# OPAMP_TESTER_2.net
KiCad netlist of a schematic drawn in Altium Designer
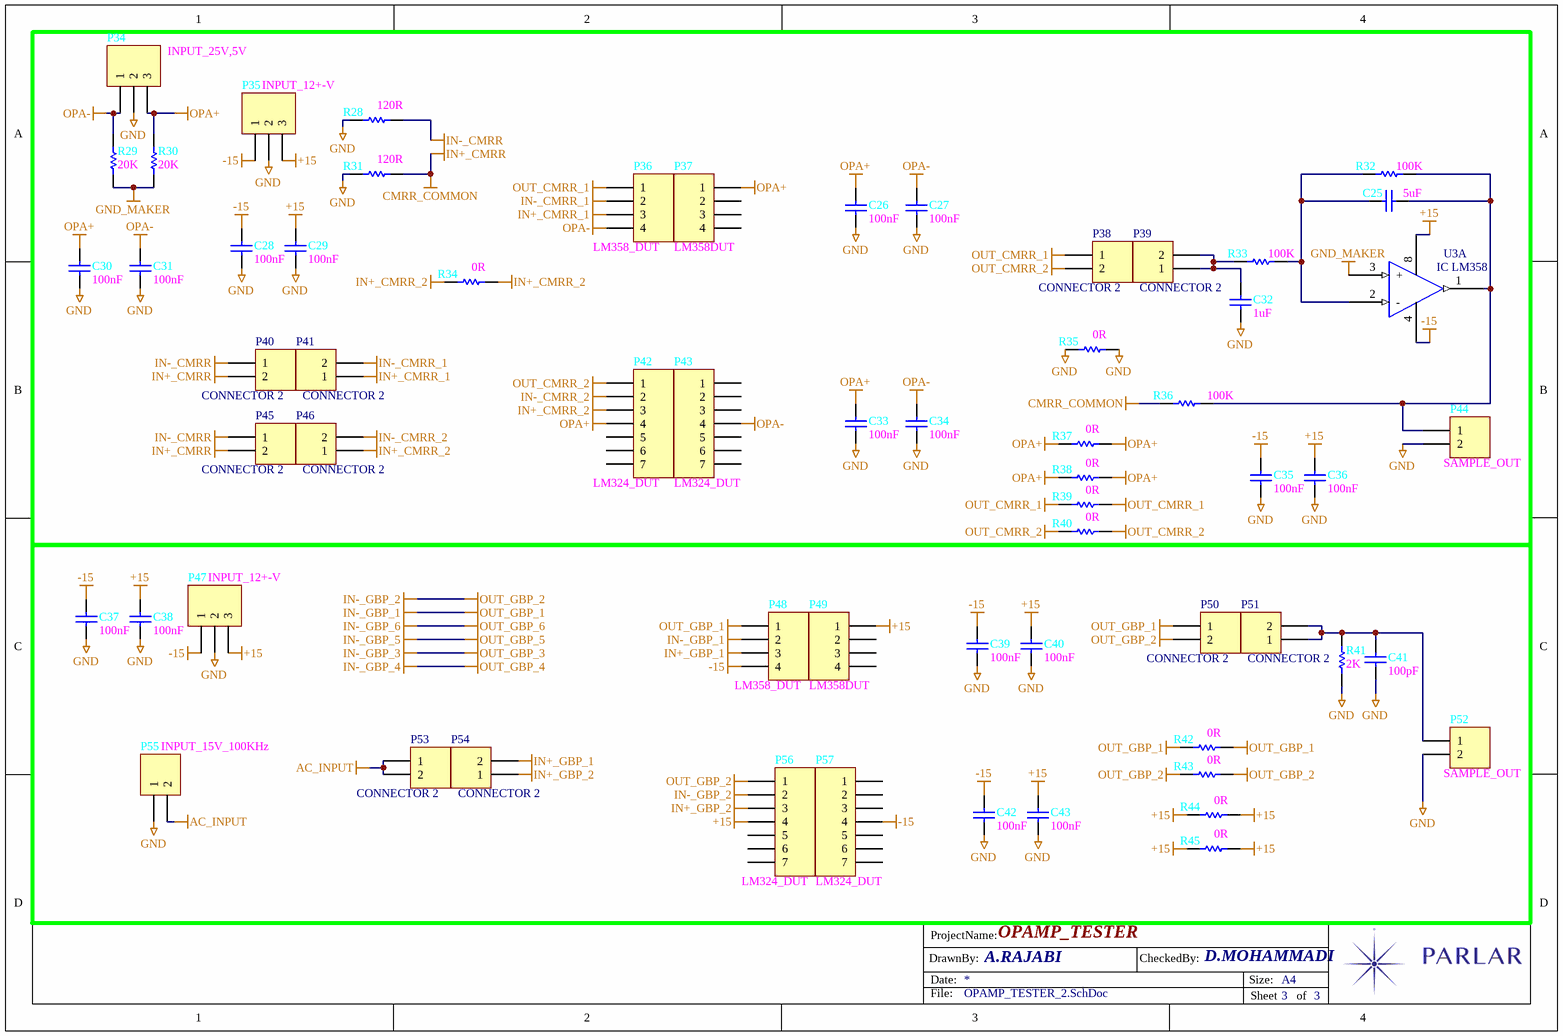
[diagram p0: OPAMP_TESTER_2.SchDoc]

(export (version "E")
  (design (tool "Eeschema 10.0.6"))
  (components
    (comp (ref "C25")
      (value "5uF")
      (footprint "SMD 1206")
      (description "Capacitor")
      (fields (field (name "PUBLISHER") "Altium Limited"))
      (libsource (lib "Parlarlib_30") (part "CAP"))
    )
    (comp (ref "C26")
      (value "100nF")
      (footprint "SMD 1206")
      (description "Capacitor")
      (fields (field (name "PUBLISHER") "Altium Limited"))
      (libsource (lib "Parlarlib_30") (part "CAP"))
    )
    (comp (ref "C27")
      (value "100nF")
      (footprint "SMD 0805")
      (description "Capacitor")
      (fields (field (name "PUBLISHER") "Altium Limited"))
      (libsource (lib "Parlarlib_30") (part "CAP"))
    )
    (comp (ref "C28")
      (value "100nF")
      (footprint "SMD 0805")
      (description "Capacitor")
      (fields (field (name "PUBLISHER") "Altium Limited"))
      (libsource (lib "Parlarlib_30") (part "CAP"))
    )
    (comp (ref "C29")
      (value "100nF")
      (footprint "SMD 0805")
      (description "Capacitor")
      (fields (field (name "PUBLISHER") "Altium Limited"))
      (libsource (lib "Parlarlib_30") (part "CAP"))
    )
    (comp (ref "C30")
      (value "100nF")
      (footprint "SMD 0805")
      (description "Capacitor")
      (fields (field (name "PUBLISHER") "Altium Limited"))
      (libsource (lib "Parlarlib_30") (part "CAP"))
    )
    (comp (ref "C31")
      (value "100nF")
      (footprint "SMD 0805")
      (description "Capacitor")
      (fields (field (name "PUBLISHER") "Altium Limited"))
      (libsource (lib "Parlarlib_30") (part "CAP"))
    )
    (comp (ref "C32")
      (value "1uF")
      (footprint "SMD 0805")
      (description "Capacitor")
      (fields (field (name "PUBLISHER") "Altium Limited"))
      (libsource (lib "Parlarlib_30") (part "CAP"))
    )
    (comp (ref "C33")
      (value "100nF")
      (footprint "SMD 1206")
      (description "Capacitor")
      (fields (field (name "PUBLISHER") "Altium Limited"))
      (libsource (lib "Parlarlib_30") (part "CAP"))
    )
    (comp (ref "C34")
      (value "100nF")
      (footprint "SMD 0805")
      (description "Capacitor")
      (fields (field (name "PUBLISHER") "Altium Limited"))
      (libsource (lib "Parlarlib_30") (part "CAP"))
    )
    (comp (ref "C35")
      (value "100nF")
      (footprint "SMD 0805")
      (description "Capacitor")
      (fields (field (name "PUBLISHER") "Altium Limited"))
      (libsource (lib "Parlarlib_30") (part "CAP"))
    )
    (comp (ref "C36")
      (value "100nF")
      (footprint "SMD 0805")
      (description "Capacitor")
      (fields (field (name "PUBLISHER") "Altium Limited"))
      (libsource (lib "Parlarlib_30") (part "CAP"))
    )
    (comp (ref "C37")
      (value "100nF")
      (footprint "SMD 0805")
      (description "Capacitor")
      (fields (field (name "PUBLISHER") "Altium Limited"))
      (libsource (lib "Parlarlib_30") (part "CAP"))
    )
    (comp (ref "C38")
      (value "100nF")
      (footprint "SMD 0805")
      (description "Capacitor")
      (fields (field (name "PUBLISHER") "Altium Limited"))
      (libsource (lib "Parlarlib_30") (part "CAP"))
    )
    (comp (ref "C39")
      (value "100nF")
      (footprint "SMD 0805")
      (description "Capacitor")
      (fields (field (name "PUBLISHER") "Altium Limited"))
      (libsource (lib "Parlarlib_30") (part "CAP"))
    )
    (comp (ref "C40")
      (value "100nF")
      (footprint "SMD 0805")
      (description "Capacitor")
      (fields (field (name "PUBLISHER") "Altium Limited"))
      (libsource (lib "Parlarlib_30") (part "CAP"))
    )
    (comp (ref "C41")
      (value "100pF")
      (footprint "SMD 0805")
      (description "Capacitor")
      (fields (field (name "PUBLISHER") "Altium Limited"))
      (libsource (lib "Parlarlib_30") (part "CAP"))
    )
    (comp (ref "C42")
      (value "100nF")
      (footprint "SMD 0805")
      (description "Capacitor")
      (fields (field (name "PUBLISHER") "Altium Limited"))
      (libsource (lib "Parlarlib_30") (part "CAP"))
    )
    (comp (ref "C43")
      (value "100nF")
      (footprint "SMD 1206")
      (description "Capacitor")
      (fields (field (name "PUBLISHER") "Altium Limited"))
      (libsource (lib "Parlarlib_30") (part "CAP"))
    )
    (comp (ref "P34")
      (value "INPUT_25V,5V")
      (footprint "CON XH 3")
      (description "Header, 3-Pin")
      (fields (field (name "PUBLISHER") "Altium Limited"))
      (libsource (lib "Parlarlib_30") (part "CONNECTOR 3"))
    )
    (comp (ref "P35")
      (value "INPUT_12+-V")
      (footprint "CON XH 3")
      (description "Header, 3-Pin")
      (fields (field (name "PUBLISHER") "Altium Limited"))
      (libsource (lib "Parlarlib_30") (part "CONNECTOR 3"))
    )
    (comp (ref "P36")
      (value "LM358_DUT")
      (footprint "CON HDR 2.54FM 4")
      (description "Header, 4-Pin")
      (fields (field (name "PUBLISHER") "Altium Limited"))
      (libsource (lib "Parlarlib_30") (part "CONNECTOR 4"))
    )
    (comp (ref "P37")
      (value "LM358DUT")
      (footprint "CON HDR 2.54FM 4")
      (description "Header, 4-Pin")
      (fields (field (name "PUBLISHER") "Altium Limited"))
      (libsource (lib "") (part "CONNECTOR 4_1"))
    )
    (comp (ref "P38")
      (value "CONNECTOR 2")
      (footprint "CON HDR 2.54M 2")
      (description "Header, 2-Pin")
      (fields (field (name "PUBLISHER") "Altium Limited"))
      (libsource (lib "") (part "CONNECTOR 2_1"))
    )
    (comp (ref "P39")
      (value "CONNECTOR 2")
      (footprint "CON HDR 2.54M 2")
      (description "Header, 2-Pin")
      (fields (field (name "PUBLISHER") "Altium Limited"))
      (libsource (lib "Parlarlib_33") (part "CONNECTOR 2"))
    )
    (comp (ref "P40")
      (value "CONNECTOR 2")
      (footprint "CON HDR 2.54M 2")
      (description "Header, 2-Pin")
      (fields (field (name "PUBLISHER") "Altium Limited"))
      (libsource (lib "") (part "CONNECTOR 2_1"))
    )
    (comp (ref "P41")
      (value "CONNECTOR 2")
      (footprint "CON HDR 2.54M 2")
      (description "Header, 2-Pin")
      (fields (field (name "PUBLISHER") "Altium Limited"))
      (libsource (lib "Parlarlib_33") (part "CONNECTOR 2"))
    )
    (comp (ref "P42")
      (value "LM324_DUT")
      (footprint "CON HDR 2.54FM 7")
      (description "Header, 7-Pin")
      (fields (field (name "PUBLISHER") "Altium Limited"))
      (libsource (lib "") (part "CONNECTOR 7_1"))
    )
    (comp (ref "P43")
      (value "LM324_DUT")
      (footprint "CON HDR 2.54FM 7")
      (description "Header, 7-Pin")
      (fields (field (name "PUBLISHER") "Altium Limited"))
      (libsource (lib "Parlarlib_30") (part "CONNECTOR 7"))
    )
    (comp (ref "P44")
      (value "SAMPLE_OUT")
      (footprint "CON XH 2")
      (description "Header, 2-Pin")
      (fields (field (name "PUBLISHER") "Altium Limited"))
      (libsource (lib "") (part "CONNECTOR 2_1"))
    )
    (comp (ref "P45")
      (value "CONNECTOR 2")
      (footprint "CON HDR 2.54M 2")
      (description "Header, 2-Pin")
      (fields (field (name "PUBLISHER") "Altium Limited"))
      (libsource (lib "") (part "CONNECTOR 2_1"))
    )
    (comp (ref "P46")
      (value "CONNECTOR 2")
      (footprint "CON HDR 2.54M 2")
      (description "Header, 2-Pin")
      (fields (field (name "PUBLISHER") "Altium Limited"))
      (libsource (lib "Parlarlib_33") (part "CONNECTOR 2"))
    )
    (comp (ref "P47")
      (value "INPUT_12+-V")
      (footprint "CON XH 3")
      (description "Header, 3-Pin")
      (fields (field (name "PUBLISHER") "Altium Limited"))
      (libsource (lib "Parlarlib_30") (part "CONNECTOR 3"))
    )
    (comp (ref "P48")
      (value "LM358_DUT")
      (footprint "CON HDR 2.54FM 4")
      (description "Header, 4-Pin")
      (fields (field (name "PUBLISHER") "Altium Limited"))
      (libsource (lib "Parlarlib_30") (part "CONNECTOR 4"))
    )
    (comp (ref "P49")
      (value "LM358DUT")
      (footprint "CON HDR 2.54FM 4")
      (description "Header, 4-Pin")
      (fields (field (name "PUBLISHER") "Altium Limited"))
      (libsource (lib "") (part "CONNECTOR 4_1"))
    )
    (comp (ref "P50")
      (value "CONNECTOR 2")
      (footprint "CON HDR 2.54M 2")
      (description "Header, 2-Pin")
      (fields (field (name "PUBLISHER") "Altium Limited"))
      (libsource (lib "") (part "CONNECTOR 2_1"))
    )
    (comp (ref "P51")
      (value "CONNECTOR 2")
      (footprint "CON HDR 2.54M 2")
      (description "Header, 2-Pin")
      (fields (field (name "PUBLISHER") "Altium Limited"))
      (libsource (lib "Parlarlib_33") (part "CONNECTOR 2"))
    )
    (comp (ref "P52")
      (value "SAMPLE_OUT")
      (footprint "CON XH 2")
      (description "Header, 2-Pin")
      (fields (field (name "PUBLISHER") "Altium Limited"))
      (libsource (lib "") (part "CONNECTOR 2_1"))
    )
    (comp (ref "P53")
      (value "CONNECTOR 2")
      (footprint "CON HDR 2.54M 2")
      (description "Header, 2-Pin")
      (fields (field (name "PUBLISHER") "Altium Limited"))
      (libsource (lib "") (part "CONNECTOR 2_1"))
    )
    (comp (ref "P54")
      (value "CONNECTOR 2")
      (footprint "CON HDR 2.54M 2")
      (description "Header, 2-Pin")
      (fields (field (name "PUBLISHER") "Altium Limited"))
      (libsource (lib "Parlarlib_33") (part "CONNECTOR 2"))
    )
    (comp (ref "P55")
      (value "INPUT_15V_100KHz")
      (footprint "CON XH 2")
      (description "Header, 2-Pin")
      (fields (field (name "PUBLISHER") "Altium Limited"))
      (libsource (lib "Parlarlib_30") (part "CONNECTOR 2"))
    )
    (comp (ref "P56")
      (value "LM324_DUT")
      (footprint "CON HDR 2.54FM 7")
      (description "Header, 7-Pin")
      (fields (field (name "PUBLISHER") "Altium Limited"))
      (libsource (lib "") (part "CONNECTOR 7_1"))
    )
    (comp (ref "P57")
      (value "LM324_DUT")
      (footprint "CON HDR 2.54FM 7")
      (description "Header, 7-Pin")
      (fields (field (name "PUBLISHER") "Altium Limited"))
      (libsource (lib "Parlarlib_30") (part "CONNECTOR 7"))
    )
    (comp (ref "R28")
      (value "120R")
      (footprint "SMD 0805")
      (description "Resistor")
      (libsource (lib "Parlarlib_30") (part "RES"))
    )
    (comp (ref "R29")
      (value "20K")
      (footprint "SMD 1206")
      (description "Resistor")
      (libsource (lib "Parlarlib_30") (part "RES"))
    )
    (comp (ref "R30")
      (value "20K")
      (footprint "SMD 0805")
      (description "Resistor")
      (libsource (lib "Parlarlib_30") (part "RES"))
    )
    (comp (ref "R31")
      (value "120R")
      (footprint "SMD 1206")
      (description "Resistor")
      (libsource (lib "Parlarlib_30") (part "RES"))
    )
    (comp (ref "R32")
      (value "100K")
      (footprint "SMD 0805")
      (description "Resistor")
      (libsource (lib "Parlarlib_30") (part "RES"))
    )
    (comp (ref "R33")
      (value "100K")
      (footprint "SMD 1206")
      (description "Resistor")
      (libsource (lib "Parlarlib_30") (part "RES"))
    )
    (comp (ref "R34")
      (value "0R")
      (footprint "SMD 1206")
      (description "Resistor")
      (libsource (lib "Parlarlib_30") (part "RES"))
    )
    (comp (ref "R35")
      (value "0R")
      (footprint "SMD 1206")
      (description "Resistor")
      (libsource (lib "Parlarlib_30") (part "RES"))
    )
    (comp (ref "R36")
      (value "100K")
      (footprint "SMD 1206")
      (description "Resistor")
      (libsource (lib "Parlarlib_30") (part "RES"))
    )
    (comp (ref "R37")
      (value "0R")
      (footprint "SMD 1206")
      (description "Resistor")
      (libsource (lib "Parlarlib_30") (part "RES"))
    )
    (comp (ref "R38")
      (value "0R")
      (footprint "SMD 1206")
      (description "Resistor")
      (libsource (lib "Parlarlib_30") (part "RES"))
    )
    (comp (ref "R39")
      (value "0R")
      (footprint "SMD 1206")
      (description "Resistor")
      (libsource (lib "Parlarlib_30") (part "RES"))
    )
    (comp (ref "R40")
      (value "0R")
      (footprint "SMD 1206")
      (description "Resistor")
      (libsource (lib "Parlarlib_30") (part "RES"))
    )
    (comp (ref "R41")
      (value "2K")
      (footprint "SMD 0805")
      (description "Resistor")
      (libsource (lib "Parlarlib_30") (part "RES"))
    )
    (comp (ref "R42")
      (value "0R")
      (footprint "SMD 1206")
      (description "Resistor")
      (libsource (lib "Parlarlib_30") (part "RES"))
    )
    (comp (ref "R43")
      (value "0R")
      (footprint "SMD 1206")
      (description "Resistor")
      (libsource (lib "Parlarlib_30") (part "RES"))
    )
    (comp (ref "R44")
      (value "0R")
      (footprint "SMD 1206")
      (description "Resistor")
      (libsource (lib "Parlarlib_30") (part "RES"))
    )
    (comp (ref "R45")
      (value "0R")
      (footprint "SMD 1206")
      (description "Resistor")
      (libsource (lib "Parlarlib_30") (part "RES"))
    )
    (comp (ref "U3")
      (value "IC LM358")
      (footprint "SMD IC SOP8")
      (libsource (lib "Parlarlib_33") (part "IC LM358"))
    )
  )
  (nets
    (net (code "1") (name "+15") (class "Default")
      (node (ref "C29") (pin "2") (pinfunction "2_2") (pintype "passive"))
      (node (ref "C36") (pin "2") (pinfunction "2_2") (pintype "passive"))
      (node (ref "C38") (pin "2") (pinfunction "2_2") (pintype "passive"))
      (node (ref "C40") (pin "2") (pinfunction "2_2") (pintype "passive"))
      (node (ref "C43") (pin "2") (pinfunction "2_2") (pintype "passive"))
      (node (ref "P35") (pin "3") (pinfunction "3_3") (pintype "passive"))
      (node (ref "P47") (pin "3") (pinfunction "3_3") (pintype "passive"))
      (node (ref "P49") (pin "1") (pinfunction "1_1") (pintype "passive"))
      (node (ref "P56") (pin "4") (pinfunction "4_4") (pintype "passive"))
      (node (ref "R44") (pin "1") (pinfunction "1_1") (pintype "passive"))
      (node (ref "R44") (pin "2") (pinfunction "2_2") (pintype "passive"))
      (node (ref "R45") (pin "1") (pinfunction "1_1") (pintype "passive"))
      (node (ref "R45") (pin "2") (pinfunction "2_2") (pintype "passive"))
      (node (ref "U3") (pin "8") (pinfunction "VCC_8") (pintype "passive"))
    )
    (net (code "2") (name "-15") (class "Default")
      (node (ref "C28") (pin "2") (pinfunction "2_2") (pintype "passive"))
      (node (ref "C35") (pin "2") (pinfunction "2_2") (pintype "passive"))
      (node (ref "C37") (pin "2") (pinfunction "2_2") (pintype "passive"))
      (node (ref "C39") (pin "2") (pinfunction "2_2") (pintype "passive"))
      (node (ref "C42") (pin "2") (pinfunction "2_2") (pintype "passive"))
      (node (ref "P35") (pin "1") (pinfunction "1_1") (pintype "passive"))
      (node (ref "P47") (pin "1") (pinfunction "1_1") (pintype "passive"))
      (node (ref "P48") (pin "4") (pinfunction "4_4") (pintype "passive"))
      (node (ref "P57") (pin "4") (pinfunction "4_4") (pintype "passive"))
      (node (ref "U3") (pin "4") (pinfunction "GND_4") (pintype "passive"))
    )
    (net (code "3") (name "AC_INPUT") (class "Default")
      (node (ref "P53") (pin "1") (pinfunction "1_1") (pintype "passive"))
      (node (ref "P53") (pin "2") (pinfunction "2_2") (pintype "passive"))
      (node (ref "P55") (pin "2") (pinfunction "2_2") (pintype "passive"))
    )
    (net (code "4") (name "CMRR_COMMON") (class "Default")
      (node (ref "P40") (pin "2") (pinfunction "2_2") (pintype "passive"))
      (node (ref "P45") (pin "2") (pinfunction "2_2") (pintype "passive"))
      (node (ref "R31") (pin "2") (pinfunction "2_2") (pintype "passive"))
      (node (ref "R36") (pin "1") (pinfunction "1_1") (pintype "passive"))
    )
    (net (code "5") (name "GND") (class "Default")
      (node (ref "C26") (pin "1") (pinfunction "1_1") (pintype "passive"))
      (node (ref "C27") (pin "1") (pinfunction "1_1") (pintype "passive"))
      (node (ref "C28") (pin "1") (pinfunction "1_1") (pintype "passive"))
      (node (ref "C29") (pin "1") (pinfunction "1_1") (pintype "passive"))
      (node (ref "C30") (pin "1") (pinfunction "1_1") (pintype "passive"))
      (node (ref "C31") (pin "1") (pinfunction "1_1") (pintype "passive"))
      (node (ref "C32") (pin "1") (pinfunction "1_1") (pintype "passive"))
      (node (ref "C33") (pin "1") (pinfunction "1_1") (pintype "passive"))
      (node (ref "C34") (pin "1") (pinfunction "1_1") (pintype "passive"))
      (node (ref "C35") (pin "1") (pinfunction "1_1") (pintype "passive"))
      (node (ref "C36") (pin "1") (pinfunction "1_1") (pintype "passive"))
      (node (ref "C37") (pin "1") (pinfunction "1_1") (pintype "passive"))
      (node (ref "C38") (pin "1") (pinfunction "1_1") (pintype "passive"))
      (node (ref "C39") (pin "1") (pinfunction "1_1") (pintype "passive"))
      (node (ref "C40") (pin "1") (pinfunction "1_1") (pintype "passive"))
      (node (ref "C41") (pin "1") (pinfunction "1_1") (pintype "passive"))
      (node (ref "C42") (pin "1") (pinfunction "1_1") (pintype "passive"))
      (node (ref "C43") (pin "1") (pinfunction "1_1") (pintype "passive"))
      (node (ref "P34") (pin "2") (pinfunction "2_2") (pintype "passive"))
      (node (ref "P35") (pin "2") (pinfunction "2_2") (pintype "passive"))
      (node (ref "P44") (pin "2") (pinfunction "2_2") (pintype "passive"))
      (node (ref "P47") (pin "2") (pinfunction "2_2") (pintype "passive"))
      (node (ref "P52") (pin "2") (pinfunction "2_2") (pintype "passive"))
      (node (ref "P55") (pin "1") (pinfunction "1_1") (pintype "passive"))
      (node (ref "R28") (pin "1") (pinfunction "1_1") (pintype "passive"))
      (node (ref "R31") (pin "1") (pinfunction "1_1") (pintype "passive"))
      (node (ref "R35") (pin "1") (pinfunction "1_1") (pintype "passive"))
      (node (ref "R35") (pin "2") (pinfunction "2_2") (pintype "passive"))
      (node (ref "R41") (pin "2") (pinfunction "2_2") (pintype "passive"))
    )
    (net (code "6") (name "GND_MAKER") (class "Default")
      (node (ref "R29") (pin "1") (pinfunction "1_1") (pintype "passive"))
      (node (ref "R30") (pin "1") (pinfunction "1_1") (pintype "passive"))
      (node (ref "U3") (pin "3") (pinfunction "+_3") (pintype "input"))
    )
    (net (code "7") (name "IN+_CMRR_1") (class "Default")
      (node (ref "P36") (pin "3") (pinfunction "3_3") (pintype "passive"))
      (node (ref "P41") (pin "1") (pinfunction "1_1") (pintype "passive"))
    )
    (net (code "8") (name "IN+_CMRR_2") (class "Default")
      (node (ref "P42") (pin "3") (pinfunction "3_3") (pintype "passive"))
      (node (ref "P46") (pin "1") (pinfunction "1_1") (pintype "passive"))
      (node (ref "R34") (pin "1") (pinfunction "1_1") (pintype "passive"))
      (node (ref "R34") (pin "2") (pinfunction "2_2") (pintype "passive"))
    )
    (net (code "9") (name "IN+_GBP_1") (class "Default")
      (node (ref "P48") (pin "3") (pinfunction "3_3") (pintype "passive"))
      (node (ref "P54") (pin "2") (pinfunction "2_2") (pintype "passive"))
    )
    (net (code "10") (name "IN+_GBP_2") (class "Default")
      (node (ref "P54") (pin "1") (pinfunction "1_1") (pintype "passive"))
      (node (ref "P56") (pin "3") (pinfunction "3_3") (pintype "passive"))
    )
    (net (code "11") (name "IN-_CMRR") (class "Default")
      (node (ref "P40") (pin "1") (pinfunction "1_1") (pintype "passive"))
      (node (ref "P45") (pin "1") (pinfunction "1_1") (pintype "passive"))
      (node (ref "R28") (pin "2") (pinfunction "2_2") (pintype "passive"))
    )
    (net (code "12") (name "IN-_CMRR_1") (class "Default")
      (node (ref "P36") (pin "2") (pinfunction "2_2") (pintype "passive"))
      (node (ref "P41") (pin "2") (pinfunction "2_2") (pintype "passive"))
    )
    (net (code "13") (name "IN-_CMRR_2") (class "Default")
      (node (ref "P42") (pin "2") (pinfunction "2_2") (pintype "passive"))
      (node (ref "P46") (pin "2") (pinfunction "2_2") (pintype "passive"))
    )
    (net (code "14") (name "IN-_GBP_1") (class "Default")
      (node (ref "P48") (pin "1") (pinfunction "1_1") (pintype "passive"))
      (node (ref "P48") (pin "2") (pinfunction "2_2") (pintype "passive"))
      (node (ref "P50") (pin "1") (pinfunction "1_1") (pintype "passive"))
      (node (ref "R42") (pin "1") (pinfunction "1_1") (pintype "passive"))
      (node (ref "R42") (pin "2") (pinfunction "2_2") (pintype "passive"))
    )
    (net (code "15") (name "IN-_GBP_2") (class "Default")
      (node (ref "P50") (pin "2") (pinfunction "2_2") (pintype "passive"))
      (node (ref "P56") (pin "1") (pinfunction "1_1") (pintype "passive"))
      (node (ref "P56") (pin "2") (pinfunction "2_2") (pintype "passive"))
      (node (ref "R43") (pin "1") (pinfunction "1_1") (pintype "passive"))
      (node (ref "R43") (pin "2") (pinfunction "2_2") (pintype "passive"))
    )
    (net (code "20") (name "Net-(C32-Pad2)") (class "Default")
      (node (ref "C32") (pin "2") (pinfunction "2_2") (pintype "passive"))
      (node (ref "P39") (pin "1") (pinfunction "1_1") (pintype "passive"))
      (node (ref "P39") (pin "2") (pinfunction "2_2") (pintype "passive"))
      (node (ref "R33") (pin "1") (pinfunction "1_1") (pintype "passive"))
    )
    (net (code "21") (name "Net-(C41-Pad2)") (class "Default")
      (node (ref "C41") (pin "2") (pinfunction "2_2") (pintype "passive"))
      (node (ref "P51") (pin "1") (pinfunction "1_1") (pintype "passive"))
      (node (ref "P51") (pin "2") (pinfunction "2_2") (pintype "passive"))
      (node (ref "P52") (pin "1") (pinfunction "1_1") (pintype "passive"))
      (node (ref "R41") (pin "1") (pinfunction "1_1") (pintype "passive"))
    )
    (net (code "22") (name "Net-(U3A--)") (class "Default")
      (node (ref "C25") (pin "2") (pinfunction "2_2") (pintype "passive"))
      (node (ref "R32") (pin "1") (pinfunction "1_1") (pintype "passive"))
      (node (ref "R33") (pin "2") (pinfunction "2_2") (pintype "passive"))
      (node (ref "U3") (pin "2") (pinfunction "-_2") (pintype "input"))
    )
    (net (code "23") (name "Net-(U3A-OUT1)") (class "Default")
      (node (ref "C25") (pin "1") (pinfunction "1_1") (pintype "passive"))
      (node (ref "P44") (pin "1") (pinfunction "1_1") (pintype "passive"))
      (node (ref "R32") (pin "2") (pinfunction "2_2") (pintype "passive"))
      (node (ref "R36") (pin "2") (pinfunction "2_2") (pintype "passive"))
      (node (ref "U3") (pin "1") (pinfunction "OUT1_1") (pintype "output"))
    )
    (net (code "24") (name "OPA+") (class "Default")
      (node (ref "C26") (pin "2") (pinfunction "2_2") (pintype "passive"))
      (node (ref "C30") (pin "2") (pinfunction "2_2") (pintype "passive"))
      (node (ref "C33") (pin "2") (pinfunction "2_2") (pintype "passive"))
      (node (ref "P34") (pin "3") (pinfunction "3_3") (pintype "passive"))
      (node (ref "P37") (pin "1") (pinfunction "1_1") (pintype "passive"))
      (node (ref "P42") (pin "4") (pinfunction "4_4") (pintype "passive"))
      (node (ref "R30") (pin "2") (pinfunction "2_2") (pintype "passive"))
      (node (ref "R37") (pin "1") (pinfunction "1_1") (pintype "passive"))
      (node (ref "R37") (pin "2") (pinfunction "2_2") (pintype "passive"))
      (node (ref "R38") (pin "1") (pinfunction "1_1") (pintype "passive"))
      (node (ref "R38") (pin "2") (pinfunction "2_2") (pintype "passive"))
    )
    (net (code "25") (name "OPA-") (class "Default")
      (node (ref "C27") (pin "2") (pinfunction "2_2") (pintype "passive"))
      (node (ref "C31") (pin "2") (pinfunction "2_2") (pintype "passive"))
      (node (ref "C34") (pin "2") (pinfunction "2_2") (pintype "passive"))
      (node (ref "P34") (pin "1") (pinfunction "1_1") (pintype "passive"))
      (node (ref "P36") (pin "4") (pinfunction "4_4") (pintype "passive"))
      (node (ref "P43") (pin "4") (pinfunction "4_4") (pintype "passive"))
      (node (ref "R29") (pin "2") (pinfunction "2_2") (pintype "passive"))
    )
    (net (code "26") (name "OUT_CMRR_1") (class "Default")
      (node (ref "P36") (pin "1") (pinfunction "1_1") (pintype "passive"))
      (node (ref "P38") (pin "1") (pinfunction "1_1") (pintype "passive"))
      (node (ref "R39") (pin "1") (pinfunction "1_1") (pintype "passive"))
      (node (ref "R39") (pin "2") (pinfunction "2_2") (pintype "passive"))
    )
    (net (code "27") (name "OUT_CMRR_2") (class "Default")
      (node (ref "P38") (pin "2") (pinfunction "2_2") (pintype "passive"))
      (node (ref "P42") (pin "1") (pinfunction "1_1") (pintype "passive"))
      (node (ref "R40") (pin "1") (pinfunction "1_1") (pintype "passive"))
      (node (ref "R40") (pin "2") (pinfunction "2_2") (pintype "passive"))
    )
    (net (code "28") (name "unconnected-(P37-Pad2)") (class "Default")
      (node (ref "P37") (pin "2") (pinfunction "2_2") (pintype "passive"))
    )
    (net (code "29") (name "unconnected-(P37-Pad3)") (class "Default")
      (node (ref "P37") (pin "3") (pinfunction "3_3") (pintype "passive"))
    )
    (net (code "30") (name "unconnected-(P37-Pad4)") (class "Default")
      (node (ref "P37") (pin "4") (pinfunction "4_4") (pintype "passive"))
    )
    (net (code "31") (name "unconnected-(P42-Pad5)") (class "Default")
      (node (ref "P42") (pin "5") (pinfunction "5_5") (pintype "passive"))
    )
    (net (code "32") (name "unconnected-(P42-Pad6)") (class "Default")
      (node (ref "P42") (pin "6") (pinfunction "6_6") (pintype "passive"))
    )
    (net (code "33") (name "unconnected-(P42-Pad7)") (class "Default")
      (node (ref "P42") (pin "7") (pinfunction "7_7") (pintype "passive"))
    )
    (net (code "34") (name "unconnected-(P43-Pad1)") (class "Default")
      (node (ref "P43") (pin "1") (pinfunction "1_1") (pintype "passive"))
    )
    (net (code "35") (name "unconnected-(P43-Pad2)") (class "Default")
      (node (ref "P43") (pin "2") (pinfunction "2_2") (pintype "passive"))
    )
    (net (code "36") (name "unconnected-(P43-Pad3)") (class "Default")
      (node (ref "P43") (pin "3") (pinfunction "3_3") (pintype "passive"))
    )
    (net (code "37") (name "unconnected-(P43-Pad5)") (class "Default")
      (node (ref "P43") (pin "5") (pinfunction "5_5") (pintype "passive"))
    )
    (net (code "38") (name "unconnected-(P43-Pad6)") (class "Default")
      (node (ref "P43") (pin "6") (pinfunction "6_6") (pintype "passive"))
    )
    (net (code "39") (name "unconnected-(P43-Pad7)") (class "Default")
      (node (ref "P43") (pin "7") (pinfunction "7_7") (pintype "passive"))
    )
    (net (code "40") (name "unconnected-(P49-Pad2)") (class "Default")
      (node (ref "P49") (pin "2") (pinfunction "2_2") (pintype "passive"))
    )
    (net (code "41") (name "unconnected-(P49-Pad3)") (class "Default")
      (node (ref "P49") (pin "3") (pinfunction "3_3") (pintype "passive"))
    )
    (net (code "42") (name "unconnected-(P49-Pad4)") (class "Default")
      (node (ref "P49") (pin "4") (pinfunction "4_4") (pintype "passive"))
    )
    (net (code "43") (name "unconnected-(P56-Pad5)") (class "Default")
      (node (ref "P56") (pin "5") (pinfunction "5_5") (pintype "passive"))
    )
    (net (code "44") (name "unconnected-(P56-Pad6)") (class "Default")
      (node (ref "P56") (pin "6") (pinfunction "6_6") (pintype "passive"))
    )
    (net (code "45") (name "unconnected-(P56-Pad7)") (class "Default")
      (node (ref "P56") (pin "7") (pinfunction "7_7") (pintype "passive"))
    )
    (net (code "46") (name "unconnected-(P57-Pad1)") (class "Default")
      (node (ref "P57") (pin "1") (pinfunction "1_1") (pintype "passive"))
    )
    (net (code "47") (name "unconnected-(P57-Pad2)") (class "Default")
      (node (ref "P57") (pin "2") (pinfunction "2_2") (pintype "passive"))
    )
    (net (code "48") (name "unconnected-(P57-Pad3)") (class "Default")
      (node (ref "P57") (pin "3") (pinfunction "3_3") (pintype "passive"))
    )
    (net (code "49") (name "unconnected-(P57-Pad5)") (class "Default")
      (node (ref "P57") (pin "5") (pinfunction "5_5") (pintype "passive"))
    )
    (net (code "50") (name "unconnected-(P57-Pad6)") (class "Default")
      (node (ref "P57") (pin "6") (pinfunction "6_6") (pintype "passive"))
    )
    (net (code "51") (name "unconnected-(P57-Pad7)") (class "Default")
      (node (ref "P57") (pin "7") (pinfunction "7_7") (pintype "passive"))
    )
  )
)
